# audiBLE_revB.net
KiCad netlist of a schematic drawn in EAGLE
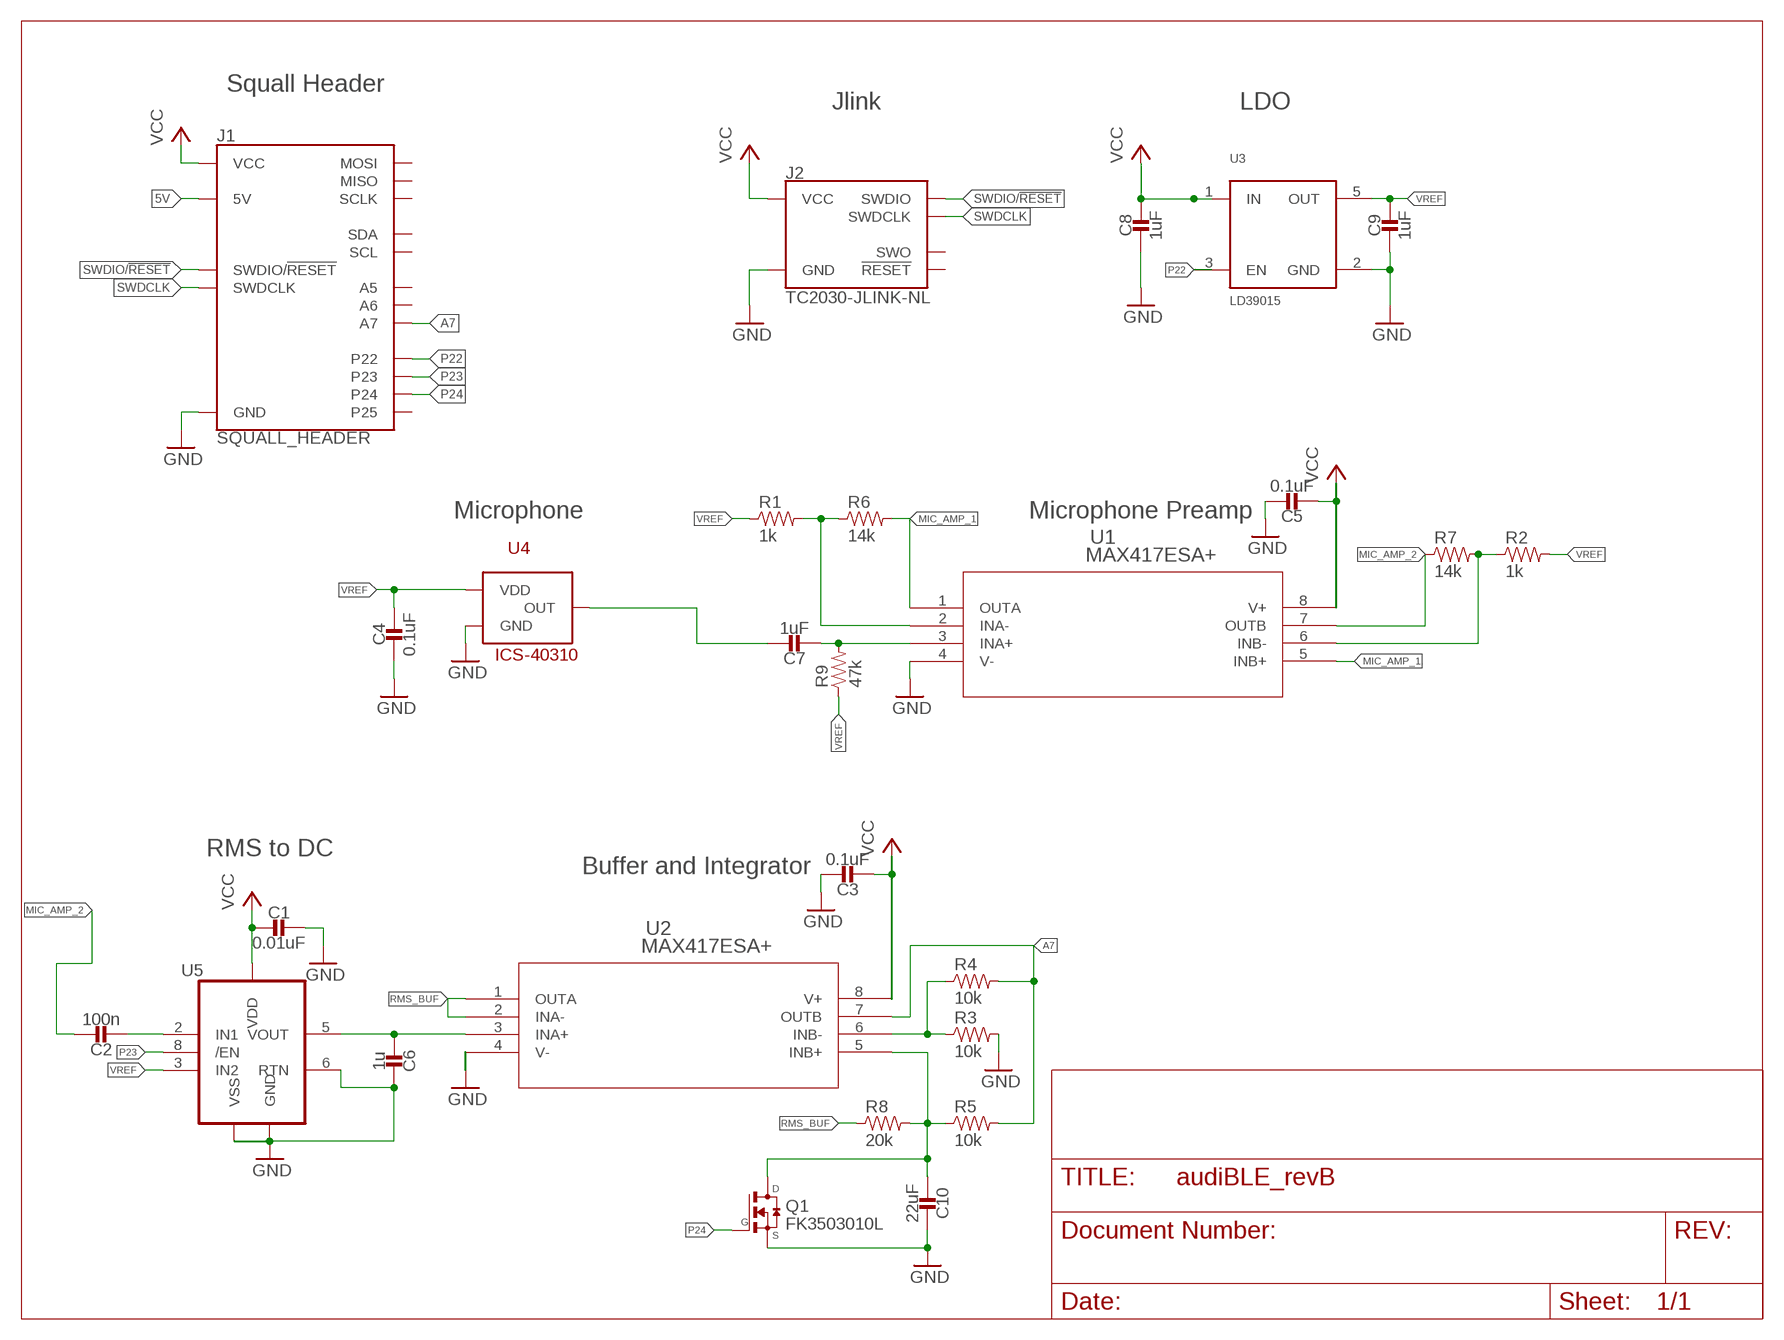
[diagram p0: schematic, sheet 1]

(export (version "E")
  (design (tool "Eeschema 10.0.6"))
  (components
    (comp (ref "C1")
      (value "0.01uF")
      (footprint "eagle-import:0402_CAP")
      (libsource (lib "eagle-import") (part "CAPACITOR"))
    )
    (comp (ref "C2")
      (value "100n")
      (footprint "eagle-import:0402_CAP")
      (libsource (lib "eagle-import") (part "CAPACITOR"))
    )
    (comp (ref "C3")
      (value "0.1uF")
      (footprint "eagle-import:0402_CAP")
      (libsource (lib "eagle-import") (part "CAPACITOR"))
    )
    (comp (ref "C4")
      (value "0.1uF")
      (footprint "eagle-import:0402_CAP")
      (libsource (lib "eagle-import") (part "CAPACITOR"))
    )
    (comp (ref "C5")
      (value "0.1uF")
      (footprint "eagle-import:0402_CAP")
      (libsource (lib "eagle-import") (part "CAPACITOR"))
    )
    (comp (ref "C6")
      (value "1u")
      (footprint "eagle-import:0402_CAP")
      (libsource (lib "eagle-import") (part "CAPACITOR"))
    )
    (comp (ref "C7")
      (value "1uF")
      (footprint "eagle-import:0402_CAP")
      (libsource (lib "eagle-import") (part "CAPACITOR"))
    )
    (comp (ref "C8")
      (value "1uF")
      (footprint "eagle-import:0402_CAP")
      (libsource (lib "eagle-import") (part "CAPACITOR"))
    )
    (comp (ref "C9")
      (value "1uF")
      (footprint "eagle-import:0402_CAP")
      (libsource (lib "eagle-import") (part "CAPACITOR"))
    )
    (comp (ref "C10")
      (value "22uF")
      (footprint "eagle-import:0402_CAP")
      (libsource (lib "eagle-import") (part "CAPACITOR"))
    )
    (comp (ref "J1")
      (value "SQUALL_HEADER")
      (footprint "eagle-import:SQUALL_HEADER")
      (libsource (lib "eagle-import") (part "SQUALL_HEADER"))
    )
    (comp (ref "J2")
      (value "TC2030-JLINK-NL")
      (footprint "eagle-import:TC2030-IDC-NL")
      (libsource (lib "eagle-import") (part "TC2030-JLINK-NL"))
    )
    (comp (ref "Q1")
      (value "FK3503010L")
      (footprint "eagle-import:SC85")
      (libsource (lib "eagle-import") (part "FK3503010L"))
    )
    (comp (ref "R1")
      (value "1k")
      (footprint "eagle-import:0402_RES")
      (libsource (lib "eagle-import") (part "RESISTOR0402_RES"))
    )
    (comp (ref "R2")
      (value "1k")
      (footprint "eagle-import:0402_RES")
      (libsource (lib "eagle-import") (part "RESISTOR0402_RES"))
    )
    (comp (ref "R3")
      (value "10k")
      (footprint "eagle-import:0402_RES")
      (libsource (lib "eagle-import") (part "RESISTOR0402_RES"))
    )
    (comp (ref "R4")
      (value "10k")
      (footprint "eagle-import:0402_RES")
      (libsource (lib "eagle-import") (part "RESISTOR0402_RES"))
    )
    (comp (ref "R5")
      (value "10k")
      (footprint "eagle-import:0402_RES")
      (libsource (lib "eagle-import") (part "RESISTOR0402_RES"))
    )
    (comp (ref "R6")
      (value "14k")
      (footprint "eagle-import:0402_RES")
      (libsource (lib "eagle-import") (part "RESISTOR0402_RES"))
    )
    (comp (ref "R7")
      (value "14k")
      (footprint "eagle-import:0402_RES")
      (libsource (lib "eagle-import") (part "RESISTOR0402_RES"))
    )
    (comp (ref "R8")
      (value "20k")
      (footprint "eagle-import:0402_RES")
      (libsource (lib "eagle-import") (part "RESISTOR0402_RES"))
    )
    (comp (ref "R9")
      (value "47k")
      (footprint "eagle-import:0402_RES")
      (libsource (lib "eagle-import") (part "RESISTOR0402_RES"))
    )
    (comp (ref "U1")
      (value "MAX417ESA+")
      (footprint "eagle-import:21-0041B_8")
      (fields (field (name "MANUFACTURER_PART_NUMBER") "max417esa+"))
      (libsource (lib "eagle-import") (part "MAX417ESA+"))
    )
    (comp (ref "U2")
      (value "MAX417ESA+")
      (footprint "eagle-import:21-0041B_8")
      (fields (field (name "MANUFACTURER_PART_NUMBER") "max417esa+"))
      (libsource (lib "eagle-import") (part "MAX417ESA+"))
    )
    (comp (ref "U3")
      (value "LD39015")
      (footprint "eagle-import:SOT-23-5")
      (libsource (lib "eagle-import") (part "LD39015"))
    )
    (comp (ref "U4")
      (value "ICS-40310")
      (footprint "eagle-import:LGA_CAV3")
      (libsource (lib "eagle-import") (part "ICS-40310"))
    )
    (comp (ref "U5")
      (value "LTC1966CMS8")
      (footprint "eagle-import:MSOP8")
      (libsource (lib "eagle-import") (part "LTC1966MS8C"))
    )
  )
  (nets
    (net (code "1") (name "/SWDIO{slash}~{RESET}") (class "Default")
      (node (ref "J1") (pin "B4") (pinfunction "SWDIO/~{RESET}_B4") (pintype "bidirectional"))
      (node (ref "J2") (pin "2") (pinfunction "SWDIO_2") (pintype "bidirectional"))
    )
    (net (code "2") (name "5V") (class "Default")
      (node (ref "J1") (pin "A5") (pinfunction "5V_A5") (pintype "bidirectional"))
      (node (ref "J1") (pin "A7") (pinfunction "5V_A7") (pintype "bidirectional"))
    )
    (net (code "3") (name "A7") (class "Default")
      (node (ref "J1") (pin "B5") (pinfunction "A7_B5") (pintype "bidirectional"))
      (node (ref "R4") (pin "2") (pinfunction "2_2") (pintype "passive"))
      (node (ref "R5") (pin "2") (pinfunction "2_2") (pintype "passive"))
      (node (ref "U2") (pin "7") (pinfunction "OUTB_7") (pintype "output"))
    )
    (net (code "4") (name "GND") (class "Default")
      (node (ref "C1") (pin "1") (pinfunction "1_1") (pintype "bidirectional"))
      (node (ref "C10") (pin "1") (pinfunction "1_1") (pintype "bidirectional"))
      (node (ref "C3") (pin "1") (pinfunction "1_1") (pintype "bidirectional"))
      (node (ref "C4") (pin "2") (pinfunction "2_2") (pintype "bidirectional"))
      (node (ref "C5") (pin "1") (pinfunction "1_1") (pintype "bidirectional"))
      (node (ref "C6") (pin "1") (pinfunction "1_1") (pintype "bidirectional"))
      (node (ref "C8") (pin "2") (pinfunction "2_2") (pintype "bidirectional"))
      (node (ref "C9") (pin "2") (pinfunction "2_2") (pintype "bidirectional"))
      (node (ref "J1") (pin "A10") (pinfunction "GND_A10") (pintype "bidirectional"))
      (node (ref "J1") (pin "A9") (pinfunction "GND_A9") (pintype "bidirectional"))
      (node (ref "J2") (pin "5") (pinfunction "GND_5") (pintype "bidirectional"))
      (node (ref "Q1") (pin "2") (pinfunction "S_2") (pintype "passive"))
      (node (ref "R3") (pin "2") (pinfunction "2_2") (pintype "passive"))
      (node (ref "U1") (pin "4") (pinfunction "V-_4") (pintype "power_in"))
      (node (ref "U2") (pin "4") (pinfunction "V-_4") (pintype "power_in"))
      (node (ref "U3") (pin "2") (pinfunction "GND_2") (pintype "bidirectional"))
      (node (ref "U4") (pin "P$2") (pinfunction "GND_P$2") (pintype "bidirectional"))
      (node (ref "U5") (pin "1") (pinfunction "GND_1") (pintype "bidirectional"))
      (node (ref "U5") (pin "4") (pinfunction "VSS_4") (pintype "bidirectional"))
      (node (ref "U5") (pin "6") (pinfunction "RTN_6") (pintype "passive"))
    )
    (net (code "5") (name "MIC_AMP_1") (class "Default")
      (node (ref "R6") (pin "2") (pinfunction "2_2") (pintype "passive"))
      (node (ref "U1") (pin "1") (pinfunction "OUTA_1") (pintype "output"))
      (node (ref "U1") (pin "5") (pinfunction "INB+_5") (pintype "input"))
    )
    (net (code "6") (name "MIC_AMP_2") (class "Default")
      (node (ref "C2") (pin "1") (pinfunction "1_1") (pintype "bidirectional"))
      (node (ref "R7") (pin "1") (pinfunction "1_1") (pintype "passive"))
      (node (ref "U1") (pin "7") (pinfunction "OUTB_7") (pintype "output"))
    )
    (net (code "7") (name "Net-(Q1-D)") (class "Default")
      (node (ref "C10") (pin "2") (pinfunction "2_2") (pintype "bidirectional"))
      (node (ref "Q1") (pin "3") (pinfunction "D_3") (pintype "passive"))
      (node (ref "R5") (pin "1") (pinfunction "1_1") (pintype "passive"))
      (node (ref "R8") (pin "2") (pinfunction "2_2") (pintype "passive"))
      (node (ref "U2") (pin "5") (pinfunction "INB+_5") (pintype "input"))
    )
    (net (code "8") (name "Net-(U1-INA+)") (class "Default")
      (node (ref "C7") (pin "2") (pinfunction "2_2") (pintype "bidirectional"))
      (node (ref "R9") (pin "2") (pinfunction "2_2") (pintype "passive"))
      (node (ref "U1") (pin "3") (pinfunction "INA+_3") (pintype "input"))
    )
    (net (code "9") (name "Net-(U1-INA-)") (class "Default")
      (node (ref "R1") (pin "2") (pinfunction "2_2") (pintype "passive"))
      (node (ref "R6") (pin "1") (pinfunction "1_1") (pintype "passive"))
      (node (ref "U1") (pin "2") (pinfunction "INA-_2") (pintype "input"))
    )
    (net (code "10") (name "Net-(U1-INB-)") (class "Default")
      (node (ref "R2") (pin "1") (pinfunction "1_1") (pintype "passive"))
      (node (ref "R7") (pin "2") (pinfunction "2_2") (pintype "passive"))
      (node (ref "U1") (pin "6") (pinfunction "INB-_6") (pintype "input"))
    )
    (net (code "11") (name "Net-(U2-INA+)") (class "Default")
      (node (ref "C6") (pin "2") (pinfunction "2_2") (pintype "bidirectional"))
      (node (ref "U2") (pin "3") (pinfunction "INA+_3") (pintype "input"))
      (node (ref "U5") (pin "5") (pinfunction "VOUT_5") (pintype "output"))
    )
    (net (code "12") (name "Net-(U2-INB-)") (class "Default")
      (node (ref "R3") (pin "1") (pinfunction "1_1") (pintype "passive"))
      (node (ref "R4") (pin "1") (pinfunction "1_1") (pintype "passive"))
      (node (ref "U2") (pin "6") (pinfunction "INB-_6") (pintype "input"))
    )
    (net (code "13") (name "Net-(U4-OUT)") (class "Default")
      (node (ref "C7") (pin "1") (pinfunction "1_1") (pintype "bidirectional"))
      (node (ref "U4") (pin "P$1") (pinfunction "OUT_P$1") (pintype "bidirectional"))
    )
    (net (code "14") (name "Net-(U5-IN1)") (class "Default")
      (node (ref "C2") (pin "2") (pinfunction "2_2") (pintype "bidirectional"))
      (node (ref "U5") (pin "2") (pinfunction "IN1_2") (pintype "input"))
    )
    (net (code "15") (name "P22") (class "Default")
      (node (ref "J1") (pin "A2") (pinfunction "P22_A2") (pintype "bidirectional"))
      (node (ref "U3") (pin "3") (pinfunction "EN_3") (pintype "bidirectional"))
    )
    (net (code "16") (name "P23") (class "Default")
      (node (ref "J1") (pin "A4") (pinfunction "P23_A4") (pintype "bidirectional"))
      (node (ref "U5") (pin "8") (pinfunction "/EN_8") (pintype "input"))
    )
    (net (code "17") (name "P24") (class "Default")
      (node (ref "J1") (pin "A6") (pinfunction "P24_A6") (pintype "bidirectional"))
      (node (ref "Q1") (pin "1") (pinfunction "G_1") (pintype "passive"))
    )
    (net (code "18") (name "RMS_BUF") (class "Default")
      (node (ref "R8") (pin "1") (pinfunction "1_1") (pintype "passive"))
      (node (ref "U2") (pin "1") (pinfunction "OUTA_1") (pintype "output"))
      (node (ref "U2") (pin "2") (pinfunction "INA-_2") (pintype "input"))
    )
    (net (code "19") (name "SWDCLK") (class "Default")
      (node (ref "J1") (pin "B2") (pinfunction "SWDCLK_B2") (pintype "bidirectional"))
      (node (ref "J2") (pin "4") (pinfunction "SWDCLK_4") (pintype "bidirectional"))
    )
    (net (code "20") (name "VCC") (class "Default")
      (node (ref "C1") (pin "2") (pinfunction "2_2") (pintype "bidirectional"))
      (node (ref "C3") (pin "2") (pinfunction "2_2") (pintype "bidirectional"))
      (node (ref "C5") (pin "2") (pinfunction "2_2") (pintype "bidirectional"))
      (node (ref "C8") (pin "1") (pinfunction "1_1") (pintype "bidirectional"))
      (node (ref "J1") (pin "A1") (pinfunction "VCC_A1") (pintype "bidirectional"))
      (node (ref "J1") (pin "A3") (pinfunction "VCC_A3") (pintype "bidirectional"))
      (node (ref "J2") (pin "1") (pinfunction "VCC_1") (pintype "bidirectional"))
      (node (ref "U1") (pin "8") (pinfunction "V+_8") (pintype "power_in"))
      (node (ref "U2") (pin "8") (pinfunction "V+_8") (pintype "power_in"))
      (node (ref "U3") (pin "1") (pinfunction "IN_1") (pintype "bidirectional"))
      (node (ref "U5") (pin "7") (pinfunction "VDD_7") (pintype "bidirectional"))
    )
    (net (code "21") (name "VREF") (class "Default")
      (node (ref "C4") (pin "1") (pinfunction "1_1") (pintype "bidirectional"))
      (node (ref "C9") (pin "1") (pinfunction "1_1") (pintype "bidirectional"))
      (node (ref "R1") (pin "1") (pinfunction "1_1") (pintype "passive"))
      (node (ref "R2") (pin "2") (pinfunction "2_2") (pintype "passive"))
      (node (ref "R9") (pin "1") (pinfunction "1_1") (pintype "passive"))
      (node (ref "U3") (pin "5") (pinfunction "OUT_5") (pintype "bidirectional"))
      (node (ref "U4") (pin "P$3") (pinfunction "VDD_P$3") (pintype "bidirectional"))
      (node (ref "U5") (pin "3") (pinfunction "IN2_3") (pintype "input"))
    )
    (net (code "22") (name "unconnected-(J1-A5-PadB9)") (class "Default")
      (node (ref "J1") (pin "B9") (pinfunction "A5_B9") (pintype "bidirectional"))
    )
    (net (code "23") (name "unconnected-(J1-A6-PadB7)") (class "Default")
      (node (ref "J1") (pin "B7") (pinfunction "A6_B7") (pintype "bidirectional"))
    )
    (net (code "24") (name "unconnected-(J1-MISO-PadB8)") (class "Default")
      (node (ref "J1") (pin "B8") (pinfunction "MISO_B8") (pintype "bidirectional"))
    )
    (net (code "25") (name "unconnected-(J1-MOSI-PadB6)") (class "Default")
      (node (ref "J1") (pin "B6") (pinfunction "MOSI_B6") (pintype "bidirectional"))
    )
    (net (code "26") (name "unconnected-(J1-P25-PadA8)") (class "Default")
      (node (ref "J1") (pin "A8") (pinfunction "P25_A8") (pintype "bidirectional"))
    )
    (net (code "27") (name "unconnected-(J1-SCL-PadB3)") (class "Default")
      (node (ref "J1") (pin "B3") (pinfunction "SCL_B3") (pintype "bidirectional"))
    )
    (net (code "28") (name "unconnected-(J1-SCLK-PadB10)") (class "Default")
      (node (ref "J1") (pin "B10") (pinfunction "SCLK_B10") (pintype "bidirectional"))
    )
    (net (code "29") (name "unconnected-(J1-SDA-PadB1)") (class "Default")
      (node (ref "J1") (pin "B1") (pinfunction "SDA_B1") (pintype "bidirectional"))
    )
    (net (code "30") (name "unconnected-(J2-SWO-Pad6)") (class "Default")
      (node (ref "J2") (pin "6") (pinfunction "SWO_6") (pintype "bidirectional"))
    )
    (net (code "31") (name "unconnected-(J2-~{RESET}-Pad3)") (class "Default")
      (node (ref "J2") (pin "3") (pinfunction "~{RESET}_3") (pintype "bidirectional"))
    )
  )
)
